# LG_TRACKER_Linear_Voltage_Regulator_3V3.net
KiCad netlist of a schematic drawn in Altium Designer
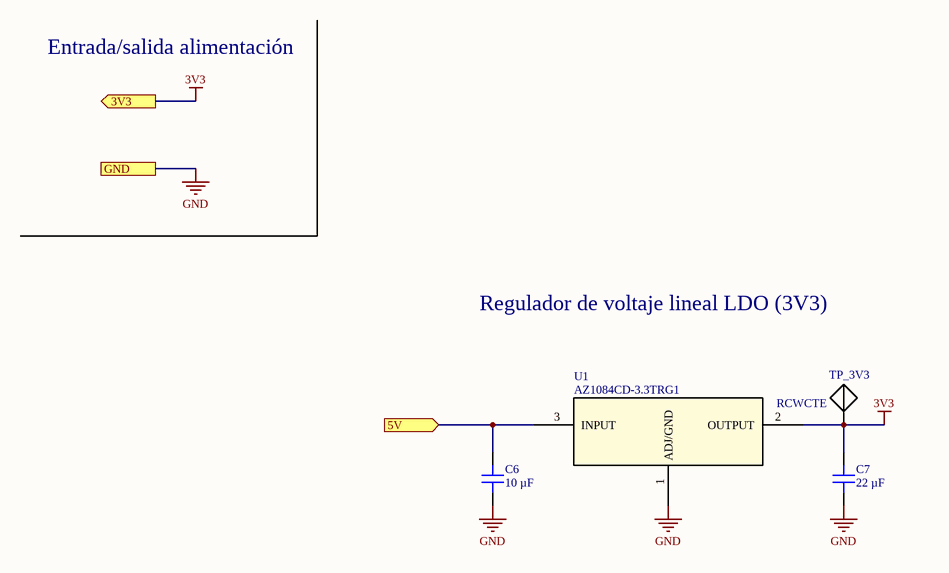
[diagram p0: LG_TRACKER_Linear_Voltage_Regulator_3V3.SchDoc]

(export (version "E")
  (design (tool "Eeschema 10.0.6"))
  (components
    (comp (ref "C6")
      (value "10 µF")
      (footprint "PCB - CAPACITOR - MLCC - CAP 1210_3225 - 1MM:CAP 1210_3225 - 1MM")
      (description "CAP CER 10UF 75V X7R 1210")
      (fields
        (field (name "PART NUMBER") "C3225X7R1N106K250AC")
        (field (name "MANUFACTURER") "TDK Corporation")
      )
      (libsource (lib "Celestial Altium Library - altium_library") (part "Capacitor"))
    )
    (comp (ref "C7")
      (value "22 µF")
      (footprint "PCB - CAPACITOR - MLCC - CAP 0805_2012:CAP 0805_2012")
      (description "CAP CER 22UF 16V X5R 0805")
      (fields
        (field (name "PART NUMBER") "CL21A226MOCLRNC")
        (field (name "MANUFACTURER") "Samsung Electro-Mechanics")
      )
      (libsource (lib "Celestial Altium Library - altium_library") (part "Capacitor"))
    )
    (comp (ref "TP_3V3")
      (value "RCWCTE")
      (footprint "RCWCTE")
      (description "- PC Test Point - - Plating Surface Mount Mounting Type")
      (fields (field (name "MF") "KOA Speer") (field (name "DIGI-KEY_PART_NUMBER") "2019-RCWCTETR-ND"))
      (libsource (lib "DIN_DC_Base_Board_components") (part "RCWCTE"))
    )
    (comp (ref "U1")
      (value "AZ1084CD-3.3TRG1")
      (footprint "TO252-3")
      (description "Fuente regulada LDO - 3V3 - 5A")
      (fields (field (name "COPYRIGHT") "Copyright (C) 2023 Ultra Librarian. All rights reserved."))
      (libsource (lib "DIN_DC_Base_Board_components_SCH_footprints") (part "AZ1084CD-3.3TRG1"))
    )
  )
  (nets
    (net (code "1") (name "/5V") (class "Default")
      (node (ref "C6") (pin "1") (pinfunction "1_1") (pintype "passive"))
      (node (ref "U1") (pin "3") (pinfunction "INPUT_3") (pintype "passive"))
    )
    (net (code "2") (name "3V3") (class "Default")
      (node (ref "C7") (pin "2") (pinfunction "2_2") (pintype "passive"))
      (node (ref "TP_3V3") (pin "1") (pinfunction "TP_1") (pintype "passive"))
      (node (ref "U1") (pin "2") (pinfunction "OUTPUT_2") (pintype "passive"))
    )
    (net (code "3") (name "GND") (class "Default")
      (node (ref "C6") (pin "2") (pinfunction "2_2") (pintype "passive"))
      (node (ref "C7") (pin "1") (pinfunction "1_1") (pintype "passive"))
      (node (ref "U1") (pin "1") (pinfunction "ADJ/GND_1") (pintype "power_in"))
    )
  )
)
